# Instrumentation_amplifier.net
KiCad netlist of a schematic drawn in Altium Designer
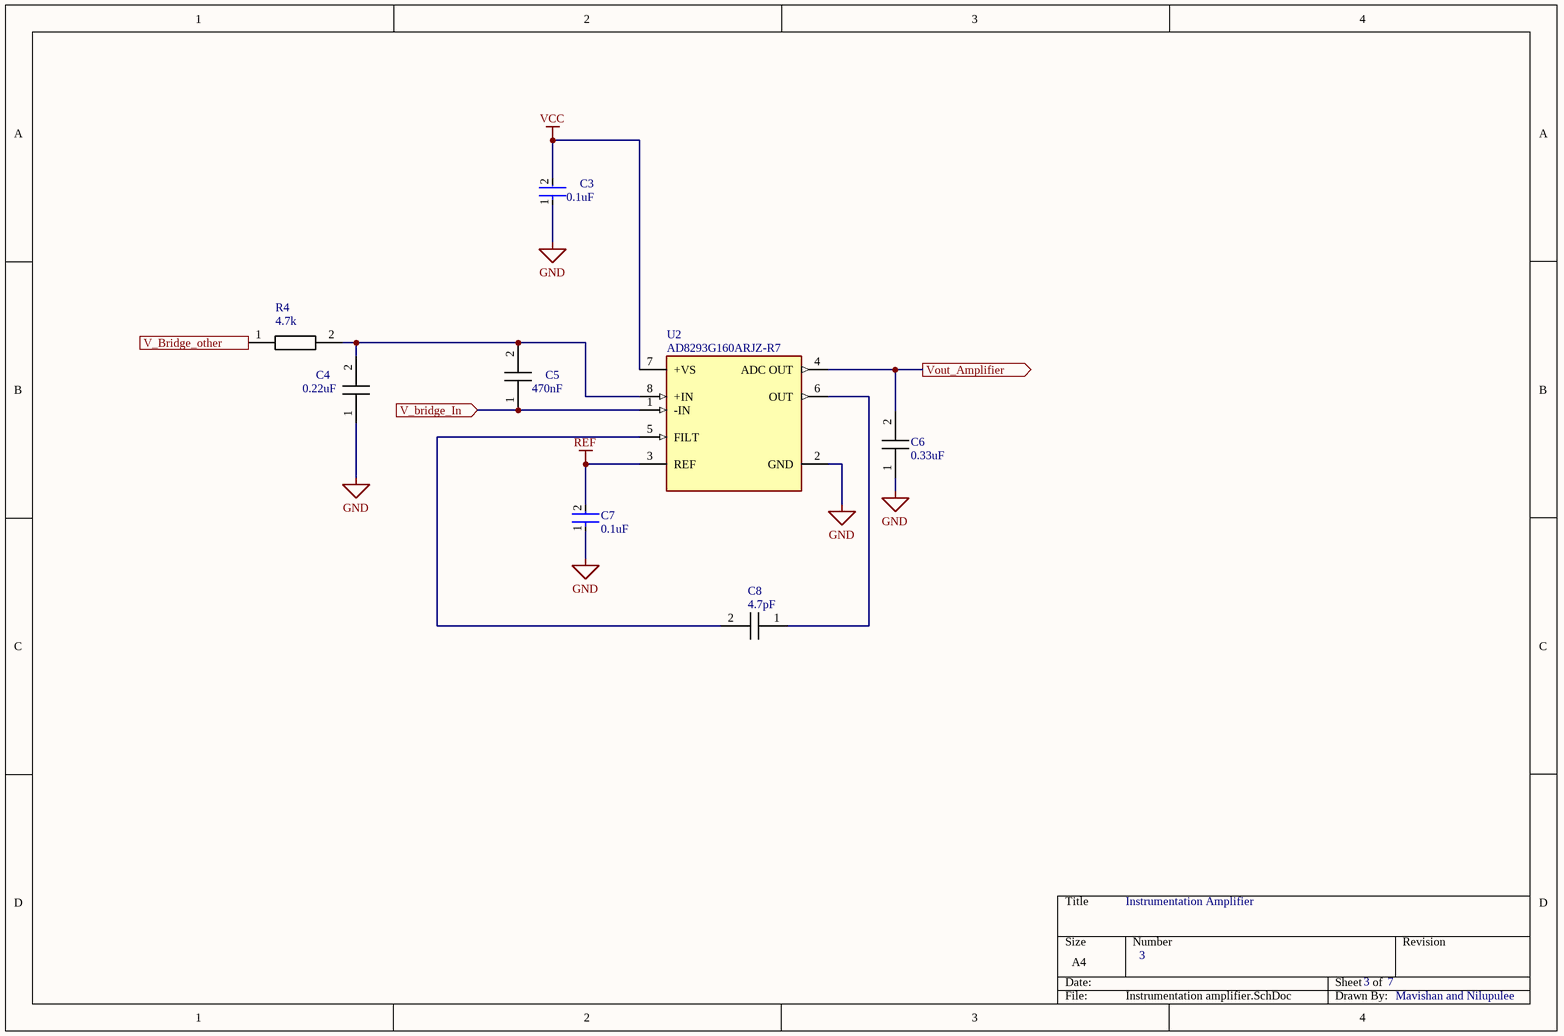
[diagram p0: Instrumentation amplifier.SchDoc]

(export (version "E")
  (design (tool "Eeschema 10.0.6"))
  (components
    (comp (ref "C3")
      (value "0.1uF")
      (footprint "FP-C1206C-EB-MFG")
      (description "CAP CER 0.1UF 25V C0G/NP0 1206")
      (fields
        (field (name "MANUFACTURER") "KEMET")
        (field (name "MANUFACTURER PART NUMBER") "C1206C104F3GACTU")
      )
      (libsource (lib "Altium Content Vault") (part "b4654b650e69147ec39a6b967a45e02"))
    )
    (comp (ref "C4")
      (value "12063C224JAT2A")
      (footprint "SamacSys:CAPC3216X94N")
      (description "Capacitor")
      (fields (field (name "MOUSER PART NUMBER") "581-12063C224JAT2A") (field (name "PARAMETER 1") "0.22uF"))
      (libsource (lib "*") (part "12063C224JAT2A"))
    )
    (comp (ref "C5")
      (value "12065C474JAT2A")
      (footprint "SamacSys:CAPC3216X152N")
      (description "Capacitor")
      (fields (field (name "MOUSER PART NUMBER") "581-12065C474J") (field (name "PARAMETER 1") "470nF"))
      (libsource (lib "*") (part "12065C474JAT2A"))
    )
    (comp (ref "C6")
      (value "12063C334MAT2A")
      (footprint "SamacSys:CAPC3216X127N")
      (description "Capacitor")
      (fields (field (name "MOUSER PART NUMBER") "581-12063C334MAT2A") (field (name "PARAMETER 1") "0.33uF"))
      (libsource (lib "*") (part "12063C334MAT2A"))
    )
    (comp (ref "C7")
      (value "0.1uF")
      (footprint "FP-C1206C-EB-MFG")
      (description "CAP CER 0.1UF 25V C0G/NP0 1206")
      (fields
        (field (name "MANUFACTURER") "KEMET")
        (field (name "MANUFACTURER PART NUMBER") "C1206C104F3GACTU")
      )
      (libsource (lib "Altium Content Vault") (part "b4654b650e69147ec39a6b967a45e02"))
    )
    (comp (ref "C8")
      (value "12063A4R7DAT2A")
      (footprint "SamacSys:CAPC3216X94N")
      (description "Capacitor")
      (fields (field (name "MOUSER PART NUMBER") "581-12063A4R7DAT2A") (field (name "PARAMETER 1") "4.7pF"))
      (libsource (lib "*") (part "12063A4R7DAT2A"))
    )
    (comp (ref "R4")
      (value "CHP1206AFX-4701ELF")
      (footprint "SamacSys:RESC3116X65N")
      (description "Resistor")
      (fields (field (name "MOUSER PART NUMBER") "652-CHP1206AFX-4701L") (field (name "PARAMETER 1") "4.7k"))
      (libsource (lib "*") (part "CHP1206AFX-4701ELF"))
    )
    (comp (ref "U2")
      (value "AD8293G160ARJZ-R7")
      (footprint "FP-RJ-8-IPC_B")
      (description "IC INST AMP 1 CIRCUIT SOT23-8")
      (libsource (lib "Altium Content Vault") (part "46add758903bcaaa27190f01554f618"))
    )
  )
  (nets
    (net (code "1") (name "/V_Bridge_other") (class "Default")
      (node (ref "R4") (pin "1") (pinfunction "1_1") (pintype "passive"))
    )
    (net (code "2") (name "/V_bridge_In") (class "Default")
      (node (ref "C5") (pin "1") (pinfunction "1_1") (pintype "passive"))
      (node (ref "U2") (pin "1") (pinfunction "-IN_1") (pintype "input"))
    )
    (net (code "3") (name "/Vout_Amplifier") (class "Default")
      (node (ref "C6") (pin "2") (pinfunction "C2_2") (pintype "passive"))
      (node (ref "U2") (pin "4") (pinfunction "ADC_OUT_4") (pintype "output"))
    )
    (net (code "4") (name "GND") (class "Default")
      (node (ref "C3") (pin "1") (pinfunction "1_1") (pintype "passive"))
      (node (ref "C4") (pin "1") (pinfunction "C1_1") (pintype "passive"))
      (node (ref "C6") (pin "1") (pinfunction "C1_1") (pintype "passive"))
      (node (ref "C7") (pin "1") (pinfunction "1_1") (pintype "passive"))
      (node (ref "U2") (pin "2") (pinfunction "GND_2") (pintype "power_in"))
    )
    (net (code "5") (name "Net-(C4-C2)") (class "Default")
      (node (ref "C4") (pin "2") (pinfunction "C2_2") (pintype "passive"))
      (node (ref "C5") (pin "2") (pinfunction "2_2") (pintype "passive"))
      (node (ref "R4") (pin "2") (pinfunction "2_2") (pintype "passive"))
      (node (ref "U2") (pin "8") (pinfunction "+IN_8") (pintype "input"))
    )
    (net (code "6") (name "Net-(U2-FILT)") (class "Default")
      (node (ref "C8") (pin "2") (pinfunction "2_2") (pintype "passive"))
      (node (ref "U2") (pin "5") (pinfunction "FILT_5") (pintype "input"))
    )
    (net (code "7") (name "Net-(U2-OUT)") (class "Default")
      (node (ref "C8") (pin "1") (pinfunction "1_1") (pintype "passive"))
      (node (ref "U2") (pin "6") (pinfunction "OUT_6") (pintype "output"))
    )
    (net (code "8") (name "REF") (class "Default")
      (node (ref "C7") (pin "2") (pinfunction "2_2") (pintype "passive"))
      (node (ref "U2") (pin "3") (pinfunction "REF_3") (pintype "power_in"))
    )
    (net (code "9") (name "VCC") (class "Default")
      (node (ref "C3") (pin "2") (pinfunction "2_2") (pintype "passive"))
      (node (ref "U2") (pin "7") (pinfunction "+VS_7") (pintype "power_in"))
    )
  )
)
